# GSM_Voltage_Translator.net
KiCad netlist of a schematic drawn in Altium Designer
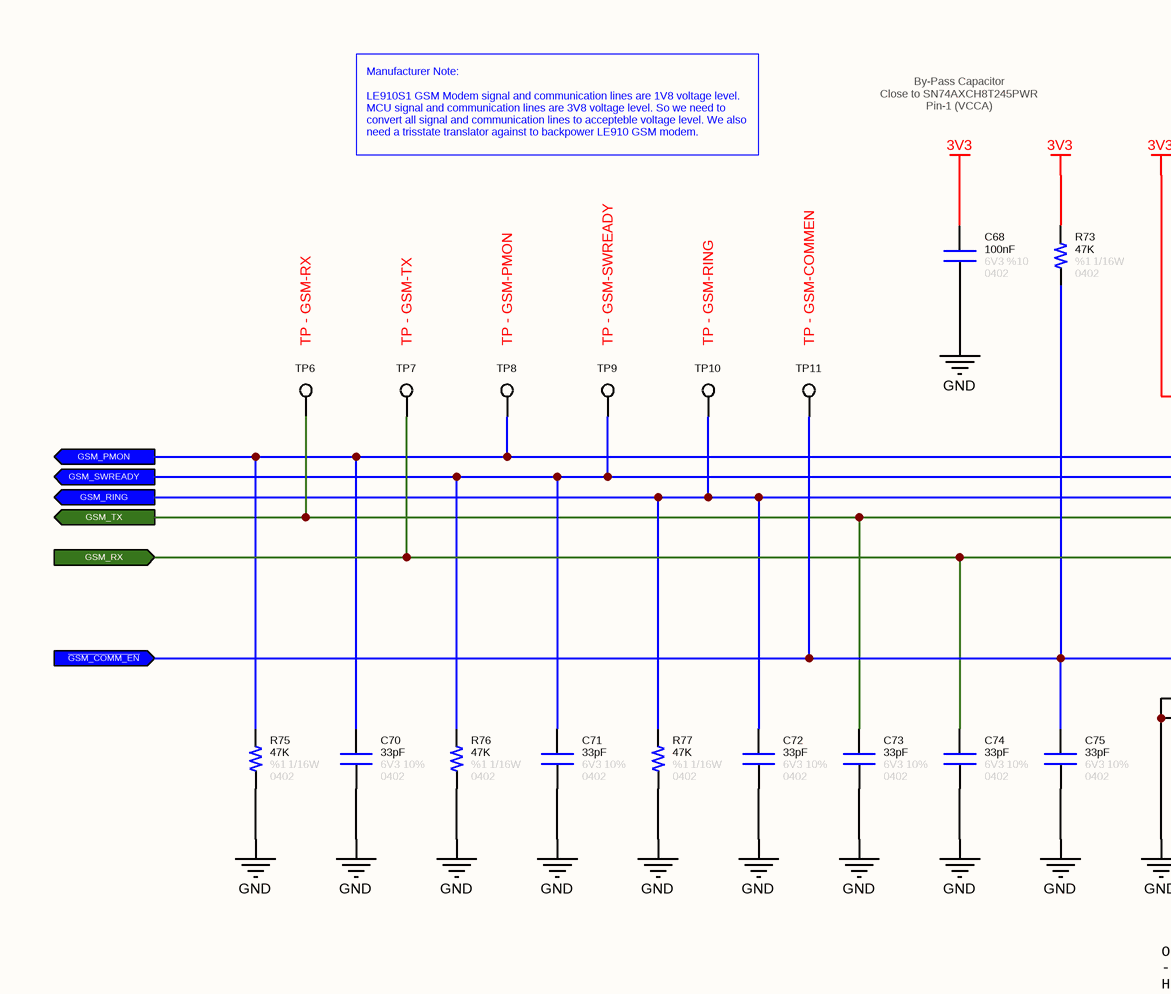
[diagram p0: GSM Voltage Translator.SchDoc, left]
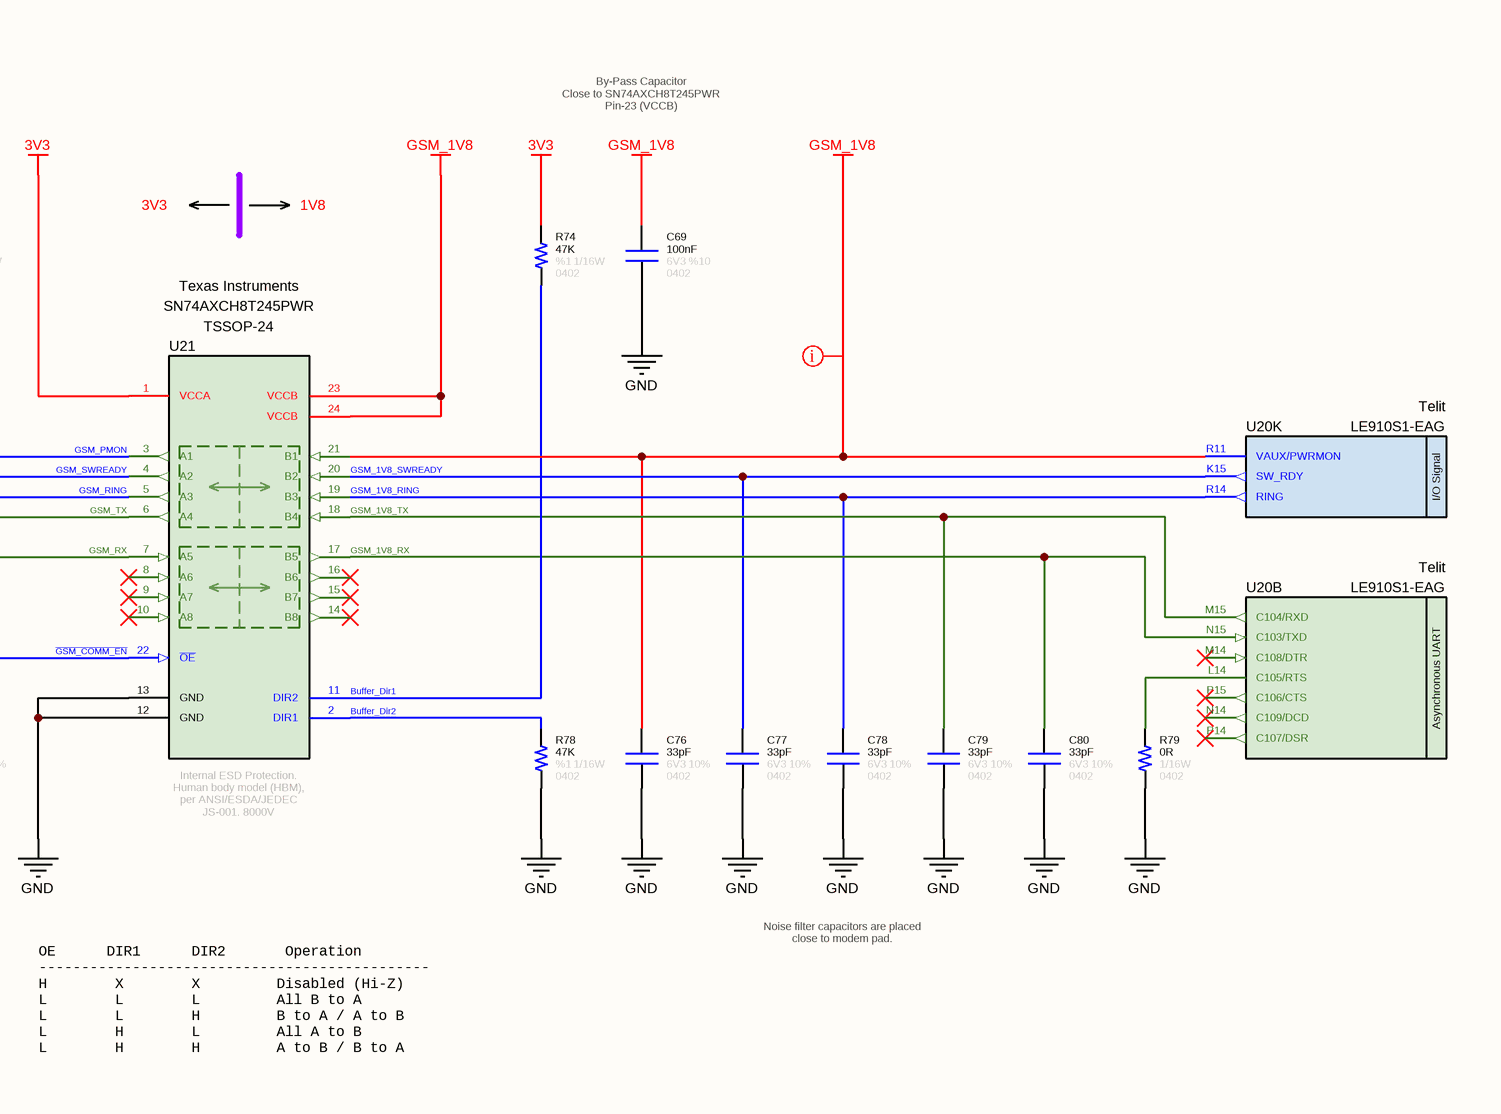
[diagram p1: GSM Voltage Translator.SchDoc, right]

(export (version "E")
  (design (tool "Eeschema 10.0.6"))
  (components
    (comp (ref "C68")
      (value "100nF")
      (footprint "CAPACITOR_0402")
      (description "Capacitor - 100nF [0402-6V3] (Ceramic)")
      (fields
        (field (name "MANUFACTURER PART NUMBER") "04026D104KAT4A")
        (field (name "TOLERANCE") "%10")
        (field (name "VOLTAGE") "6V3")
        (field (name "CASE") "0402")
        (field (name "Comment") "Capacitor - 100nF [0402] (Ceramic)")
      )
      (libsource (lib "Akkoyun") (part "Capacitor - 100nF [0402-6V3]"))
    )
    (comp (ref "C69")
      (value "100nF")
      (footprint "CAPACITOR_0402")
      (description "Capacitor - 100nF [0402-6V3] (Ceramic)")
      (fields
        (field (name "MANUFACTURER PART NUMBER") "04026D104KAT4A")
        (field (name "TOLERANCE") "%10")
        (field (name "VOLTAGE") "6V3")
        (field (name "CASE") "0402")
        (field (name "Comment") "Capacitor - 100nF [0402] (Ceramic)")
      )
      (libsource (lib "Akkoyun") (part "Capacitor - 100nF [0402-6V3]"))
    )
    (comp (ref "C70")
      (value "33pF")
      (footprint "CAPACITOR_0402")
      (description "Capacitor - 33pF [0402] (Ceramic)")
      (fields
        (field (name "MANUFACTURER PART NUMBER") "C0402C330J9RACAUTO")
        (field (name "TOLERANCE") "10%")
        (field (name "CASE") "0402")
        (field (name "VOLTAGE") "6V3")
      )
      (libsource (lib "Akkoyun") (part "Capacitor - 33pF [0402-6V3]"))
    )
    (comp (ref "C71")
      (value "33pF")
      (footprint "CAPACITOR_0402")
      (description "Capacitor - 33pF [0402] (Ceramic)")
      (fields
        (field (name "MANUFACTURER PART NUMBER") "C0402C330J9RACAUTO")
        (field (name "TOLERANCE") "10%")
        (field (name "CASE") "0402")
        (field (name "VOLTAGE") "6V3")
      )
      (libsource (lib "Akkoyun") (part "Capacitor - 33pF [0402-6V3]"))
    )
    (comp (ref "C72")
      (value "33pF")
      (footprint "CAPACITOR_0402")
      (description "Capacitor - 33pF [0402] (Ceramic)")
      (fields
        (field (name "MANUFACTURER PART NUMBER") "C0402C330J9RACAUTO")
        (field (name "TOLERANCE") "10%")
        (field (name "CASE") "0402")
        (field (name "VOLTAGE") "6V3")
      )
      (libsource (lib "Akkoyun") (part "Capacitor - 33pF [0402-6V3]"))
    )
    (comp (ref "C73")
      (value "33pF")
      (footprint "CAPACITOR_0402")
      (description "Capacitor - 33pF [0402] (Ceramic)")
      (fields
        (field (name "MANUFACTURER PART NUMBER") "C0402C330J9RACAUTO")
        (field (name "TOLERANCE") "10%")
        (field (name "CASE") "0402")
        (field (name "VOLTAGE") "6V3")
      )
      (libsource (lib "Akkoyun") (part "Capacitor - 33pF [0402-6V3]"))
    )
    (comp (ref "C74")
      (value "33pF")
      (footprint "CAPACITOR_0402")
      (description "Capacitor - 33pF [0402] (Ceramic)")
      (fields
        (field (name "MANUFACTURER PART NUMBER") "C0402C330J9RACAUTO")
        (field (name "TOLERANCE") "10%")
        (field (name "CASE") "0402")
        (field (name "VOLTAGE") "6V3")
      )
      (libsource (lib "Akkoyun") (part "Capacitor - 33pF [0402-6V3]"))
    )
    (comp (ref "C75")
      (value "33pF")
      (footprint "CAPACITOR_0402")
      (description "Capacitor - 33pF [0402] (Ceramic)")
      (fields
        (field (name "MANUFACTURER PART NUMBER") "C0402C330J9RACAUTO")
        (field (name "TOLERANCE") "10%")
        (field (name "CASE") "0402")
        (field (name "VOLTAGE") "6V3")
      )
      (libsource (lib "Akkoyun") (part "Capacitor - 33pF [0402-6V3]"))
    )
    (comp (ref "C76")
      (value "33pF")
      (footprint "CAPACITOR_0402")
      (description "Capacitor - 33pF [0402] (Ceramic)")
      (fields
        (field (name "MANUFACTURER PART NUMBER") "C0402C330J9RACAUTO")
        (field (name "TOLERANCE") "10%")
        (field (name "CASE") "0402")
        (field (name "VOLTAGE") "6V3")
      )
      (libsource (lib "Akkoyun") (part "Capacitor - 33pF [0402-6V3]"))
    )
    (comp (ref "C77")
      (value "33pF")
      (footprint "CAPACITOR_0402")
      (description "Capacitor - 33pF [0402] (Ceramic)")
      (fields
        (field (name "MANUFACTURER PART NUMBER") "C0402C330J9RACAUTO")
        (field (name "TOLERANCE") "10%")
        (field (name "CASE") "0402")
        (field (name "VOLTAGE") "6V3")
      )
      (libsource (lib "Akkoyun") (part "Capacitor - 33pF [0402-6V3]"))
    )
    (comp (ref "C78")
      (value "33pF")
      (footprint "CAPACITOR_0402")
      (description "Capacitor - 33pF [0402] (Ceramic)")
      (fields
        (field (name "MANUFACTURER PART NUMBER") "C0402C330J9RACAUTO")
        (field (name "TOLERANCE") "10%")
        (field (name "CASE") "0402")
        (field (name "VOLTAGE") "6V3")
      )
      (libsource (lib "Akkoyun") (part "Capacitor - 33pF [0402-6V3]"))
    )
    (comp (ref "C79")
      (value "33pF")
      (footprint "CAPACITOR_0402")
      (description "Capacitor - 33pF [0402] (Ceramic)")
      (fields
        (field (name "MANUFACTURER PART NUMBER") "C0402C330J9RACAUTO")
        (field (name "TOLERANCE") "10%")
        (field (name "CASE") "0402")
        (field (name "VOLTAGE") "6V3")
      )
      (libsource (lib "Akkoyun") (part "Capacitor - 33pF [0402-6V3]"))
    )
    (comp (ref "C80")
      (value "33pF")
      (footprint "CAPACITOR_0402")
      (description "Capacitor - 33pF [0402] (Ceramic)")
      (fields
        (field (name "MANUFACTURER PART NUMBER") "C0402C330J9RACAUTO")
        (field (name "TOLERANCE") "10%")
        (field (name "CASE") "0402")
        (field (name "VOLTAGE") "6V3")
      )
      (libsource (lib "Akkoyun") (part "Capacitor - 33pF [0402-6V3]"))
    )
    (comp (ref "R73")
      (value "47K")
      (footprint "RESISTOR_0402")
      (description "Thick Film Resistors - SMD 1/16 W 47 KOhm 1%")
      (fields
        (field (name "MANUFACTURER PART NUMBER") "CRCW040247K0FKED")
        (field (name "TOLERANCE") "%1")
        (field (name "CASE") "0402")
        (field (name "POWER") "1/16W")
        (field (name "Comment") "47K - 0402 - %1 - 1/16W")
      )
      (libsource (lib "Akkoyun") (part "Resistor - 47K [0402]"))
    )
    (comp (ref "R74")
      (value "47K")
      (footprint "RESISTOR_0402")
      (description "Thick Film Resistors - SMD 1/16 W 47 KOhm 1%")
      (fields
        (field (name "MANUFACTURER PART NUMBER") "CRCW040247K0FKED")
        (field (name "TOLERANCE") "%1")
        (field (name "CASE") "0402")
        (field (name "POWER") "1/16W")
        (field (name "Comment") "47K - 0402 - %1 - 1/16W")
      )
      (libsource (lib "Akkoyun") (part "Resistor - 47K [0402]"))
    )
    (comp (ref "R75")
      (value "47K")
      (footprint "RESISTOR_0402")
      (description "Thick Film Resistors - SMD 1/16 W 47 KOhm 1%")
      (fields
        (field (name "MANUFACTURER PART NUMBER") "CRCW040247K0FKED")
        (field (name "TOLERANCE") "%1")
        (field (name "CASE") "0402")
        (field (name "POWER") "1/16W")
        (field (name "Comment") "47K - 0402 - %1 - 1/16W")
      )
      (libsource (lib "Akkoyun") (part "Resistor - 47K [0402]"))
    )
    (comp (ref "R76")
      (value "47K")
      (footprint "RESISTOR_0402")
      (description "Thick Film Resistors - SMD 1/16 W 47 KOhm 1%")
      (fields
        (field (name "MANUFACTURER PART NUMBER") "CRCW040247K0FKED")
        (field (name "TOLERANCE") "%1")
        (field (name "CASE") "0402")
        (field (name "POWER") "1/16W")
        (field (name "Comment") "47K - 0402 - %1 - 1/16W")
      )
      (libsource (lib "Akkoyun") (part "Resistor - 47K [0402]"))
    )
    (comp (ref "R77")
      (value "47K")
      (footprint "RESISTOR_0402")
      (description "Thick Film Resistors - SMD 1/16 W 47 KOhm 1%")
      (fields
        (field (name "MANUFACTURER PART NUMBER") "CRCW040247K0FKED")
        (field (name "TOLERANCE") "%1")
        (field (name "CASE") "0402")
        (field (name "POWER") "1/16W")
        (field (name "Comment") "47K - 0402 - %1 - 1/16W")
      )
      (libsource (lib "Akkoyun") (part "Resistor - 47K [0402]"))
    )
    (comp (ref "R78")
      (value "47K")
      (footprint "RESISTOR_0402")
      (description "Thick Film Resistors - SMD 1/16 W 47 KOhm 1%")
      (fields
        (field (name "MANUFACTURER PART NUMBER") "CRCW040247K0FKED")
        (field (name "TOLERANCE") "%1")
        (field (name "CASE") "0402")
        (field (name "POWER") "1/16W")
        (field (name "Comment") "47K - 0402 - %1 - 1/16W")
      )
      (libsource (lib "Akkoyun") (part "Resistor - 47K [0402]"))
    )
    (comp (ref "R79")
      (value "0R")
      (footprint "RESISTOR_0402")
      (description "Thick Film Resistors - SMD 1/16 W 0 Ohm")
      (fields
        (field (name "MANUFACTURER PART NUMBER") "CRCW04020000Z0ED")
        (field (name "CASE") "0402")
        (field (name "POWER") "1/16W")
        (field (name "Comment") "0R - 0402 - %1 - 1/16W")
      )
      (libsource (lib "Akkoyun") (part "Resistor - 0R [0402]"))
    )
    (comp (ref "TP6")
      (value "TP - GSM-RX")
      (footprint "TP")
      (description "Test Point")
      (libsource (lib "Akkoyun") (part "PCB - Test Point"))
    )
    (comp (ref "TP7")
      (value "TP - GSM-TX")
      (footprint "TP")
      (description "Test Point")
      (libsource (lib "Akkoyun") (part "PCB - Test Point"))
    )
    (comp (ref "TP8")
      (value "TP - GSM-PMON")
      (footprint "TP")
      (description "Test Point")
      (libsource (lib "Akkoyun") (part "PCB - Test Point"))
    )
    (comp (ref "TP9")
      (value "TP - GSM-SWREADY")
      (footprint "TP")
      (description "Test Point")
      (libsource (lib "Akkoyun") (part "PCB - Test Point"))
    )
    (comp (ref "TP10")
      (value "TP - GSM-RING")
      (footprint "TP")
      (description "Test Point")
      (libsource (lib "Akkoyun") (part "PCB - Test Point"))
    )
    (comp (ref "TP11")
      (value "TP - GSM-COMMEN")
      (footprint "TP")
      (description "Test Point")
      (libsource (lib "Akkoyun") (part "PCB - Test Point"))
    )
    (comp (ref "U20")
      (value "LE910S1-EAG LTE GSM Module")
      (footprint "LE910 GSM Modem")
      (description "Telit LE910S1-EAG GPRS/GNSS Module")
      (fields
        (field (name "MANUFACTURER PART NUMBER") "LE910S1-EAG")
        (field (name "MANUFACTURER NAME") "Telit")
      )
      (libsource (lib "Akkoyun") (part "IC - LE910S1-EAG"))
    )
    (comp (ref "U21")
      (value "SN74AXCH8T245PWR")
      (footprint "TSSOP-24")
      (description "Translation - Voltage Levels 8-Bit Dual-Supply Bus Transceiver 24-TSSOP -40 to 125")
      (fields
        (field (name "MANUFACTURER NAME") "Texas Instruments")
        (field (name "MANUFACTURER PART NUMBER") "SN74AXCH8T245PWR")
        (field (name "CASE") "TSSOP-24")
      )
      (libsource (lib "Akkoyun") (part "IC - SN74AXCH8T245PWR"))
    )
  )
  (nets
    (net (code "1") (name "/Buffer_Dir1") (class "Default")
      (node (ref "R74") (pin "1") (pinfunction "1_1") (pintype "passive"))
      (node (ref "U21") (pin "11") (pinfunction "DIR2_11") (pintype "passive"))
    )
    (net (code "2") (name "/Buffer_Dir2") (class "Default")
      (node (ref "R78") (pin "2") (pinfunction "2_2") (pintype "passive"))
      (node (ref "U21") (pin "2") (pinfunction "DIR1_2") (pintype "passive"))
    )
    (net (code "3") (name "/GSM_1V8_RING") (class "Default")
      (node (ref "C78") (pin "2") (pinfunction "2_2") (pintype "passive"))
      (node (ref "U20") (pin "R14") (pinfunction "RING_R14") (pintype "output"))
      (node (ref "U21") (pin "19") (pinfunction "B3_19") (pintype "input"))
    )
    (net (code "4") (name "/GSM_1V8_RX") (class "Default")
      (node (ref "C80") (pin "2") (pinfunction "2_2") (pintype "passive"))
      (node (ref "U20") (pin "N15") (pinfunction "C103/TXD_N15") (pintype "input"))
      (node (ref "U21") (pin "17") (pinfunction "B5_17") (pintype "output"))
    )
    (net (code "5") (name "/GSM_1V8_SWREADY") (class "Default")
      (node (ref "C77") (pin "2") (pinfunction "2_2") (pintype "passive"))
      (node (ref "U20") (pin "K15") (pinfunction "SW_RDY_K15") (pintype "output"))
      (node (ref "U21") (pin "20") (pinfunction "B2_20") (pintype "input"))
    )
    (net (code "6") (name "/GSM_1V8_TX") (class "Default")
      (node (ref "C79") (pin "2") (pinfunction "2_2") (pintype "passive"))
      (node (ref "U20") (pin "M15") (pinfunction "C104/RXD_M15") (pintype "output"))
      (node (ref "U21") (pin "18") (pinfunction "B4_18") (pintype "input"))
    )
    (net (code "7") (name "/GSM_PMON") (class "Default")
      (node (ref "C70") (pin "2") (pinfunction "2_2") (pintype "passive"))
      (node (ref "R75") (pin "2") (pinfunction "2_2") (pintype "passive"))
      (node (ref "TP8") (pin "1") (pinfunction "1_1") (pintype "passive"))
      (node (ref "U21") (pin "3") (pinfunction "A1_3") (pintype "output"))
    )
    (net (code "8") (name "/GSM_RING") (class "Default")
      (node (ref "C72") (pin "2") (pinfunction "2_2") (pintype "passive"))
      (node (ref "R77") (pin "2") (pinfunction "2_2") (pintype "passive"))
      (node (ref "TP10") (pin "1") (pinfunction "1_1") (pintype "passive"))
      (node (ref "U21") (pin "5") (pinfunction "A3_5") (pintype "output"))
    )
    (net (code "9") (name "/GSM_RX") (class "Default")
      (node (ref "C74") (pin "2") (pinfunction "2_2") (pintype "passive"))
      (node (ref "TP7") (pin "1") (pinfunction "1_1") (pintype "passive"))
      (node (ref "U21") (pin "7") (pinfunction "A5_7") (pintype "input"))
    )
    (net (code "10") (name "/GSM_SWREADY") (class "Default")
      (node (ref "C71") (pin "2") (pinfunction "2_2") (pintype "passive"))
      (node (ref "R76") (pin "2") (pinfunction "2_2") (pintype "passive"))
      (node (ref "TP9") (pin "1") (pinfunction "1_1") (pintype "passive"))
      (node (ref "U21") (pin "4") (pinfunction "A2_4") (pintype "output"))
    )
    (net (code "11") (name "/GSM_TX") (class "Default")
      (node (ref "C73") (pin "2") (pinfunction "2_2") (pintype "passive"))
      (node (ref "TP6") (pin "1") (pinfunction "1_1") (pintype "passive"))
      (node (ref "U21") (pin "6") (pinfunction "A4_6") (pintype "output"))
    )
    (net (code "12") (name "/~{GSM_COMM_EN}") (class "Default")
      (node (ref "C75") (pin "2") (pinfunction "2_2") (pintype "passive"))
      (node (ref "R73") (pin "1") (pinfunction "1_1") (pintype "passive"))
      (node (ref "TP11") (pin "1") (pinfunction "1_1") (pintype "passive"))
      (node (ref "U21") (pin "22") (pinfunction "~{OE}_22") (pintype "input"))
    )
    (net (code "13") (name "3V3") (class "Default")
      (node (ref "C68") (pin "2") (pinfunction "2_2") (pintype "passive"))
      (node (ref "R73") (pin "2") (pinfunction "2_2") (pintype "passive"))
      (node (ref "R74") (pin "2") (pinfunction "2_2") (pintype "passive"))
      (node (ref "U21") (pin "1") (pinfunction "VCCA_1") (pintype "power_in"))
    )
    (net (code "14") (name "GND") (class "Default")
      (node (ref "C68") (pin "1") (pinfunction "1_1") (pintype "passive"))
      (node (ref "C69") (pin "1") (pinfunction "1_1") (pintype "passive"))
      (node (ref "C70") (pin "1") (pinfunction "1_1") (pintype "passive"))
      (node (ref "C71") (pin "1") (pinfunction "1_1") (pintype "passive"))
      (node (ref "C72") (pin "1") (pinfunction "1_1") (pintype "passive"))
      (node (ref "C73") (pin "1") (pinfunction "1_1") (pintype "passive"))
      (node (ref "C74") (pin "1") (pinfunction "1_1") (pintype "passive"))
      (node (ref "C75") (pin "1") (pinfunction "1_1") (pintype "passive"))
      (node (ref "C76") (pin "1") (pinfunction "1_1") (pintype "passive"))
      (node (ref "C77") (pin "1") (pinfunction "1_1") (pintype "passive"))
      (node (ref "C78") (pin "1") (pinfunction "1_1") (pintype "passive"))
      (node (ref "C79") (pin "1") (pinfunction "1_1") (pintype "passive"))
      (node (ref "C80") (pin "1") (pinfunction "1_1") (pintype "passive"))
      (node (ref "R75") (pin "1") (pinfunction "1_1") (pintype "passive"))
      (node (ref "R76") (pin "1") (pinfunction "1_1") (pintype "passive"))
      (node (ref "R77") (pin "1") (pinfunction "1_1") (pintype "passive"))
      (node (ref "R78") (pin "1") (pinfunction "1_1") (pintype "passive"))
      (node (ref "R79") (pin "1") (pinfunction "1_1") (pintype "passive"))
      (node (ref "U21") (pin "12") (pinfunction "GND_12") (pintype "power_in"))
      (node (ref "U21") (pin "13") (pinfunction "GND_13") (pintype "power_in"))
    )
    (net (code "15") (name "GSM_1V8") (class "Default")
      (node (ref "C69") (pin "2") (pinfunction "2_2") (pintype "passive"))
      (node (ref "C76") (pin "2") (pinfunction "2_2") (pintype "passive"))
      (node (ref "U20") (pin "R11") (pinfunction "VAUX/PWRMON_R11") (pintype "power_in"))
      (node (ref "U21") (pin "21") (pinfunction "B1_21") (pintype "input"))
      (node (ref "U21") (pin "23") (pinfunction "VCCB_23") (pintype "power_in"))
      (node (ref "U21") (pin "24") (pinfunction "VCCB_24") (pintype "power_in"))
    )
    (net (code "16") (name "Net-(U20B-C105{slash}RTS)") (class "Default")
      (node (ref "R79") (pin "2") (pinfunction "2_2") (pintype "passive"))
      (node (ref "U20") (pin "L14") (pinfunction "C105/RTS_L14") (pintype "open_collector"))
    )
    (net (code "17") (name "unconnected-(U20B-C106{slash}CTS-PadP15)") (class "Default")
      (node (ref "U20") (pin "P15") (pinfunction "C106/CTS_P15") (pintype "output+no_connect"))
    )
    (net (code "18") (name "unconnected-(U20B-C107{slash}DSR-PadP14)") (class "Default")
      (node (ref "U20") (pin "P14") (pinfunction "C107/DSR_P14") (pintype "output+no_connect"))
    )
    (net (code "19") (name "unconnected-(U20B-C108{slash}DTR-PadM14)") (class "Default")
      (node (ref "U20") (pin "M14") (pinfunction "C108/DTR_M14") (pintype "input+no_connect"))
    )
    (net (code "20") (name "unconnected-(U20B-C109{slash}DCD-PadN14)") (class "Default")
      (node (ref "U20") (pin "N14") (pinfunction "C109/DCD_N14") (pintype "output+no_connect"))
    )
    (net (code "21") (name "unconnected-(U21-A6-Pad8)") (class "Default")
      (node (ref "U21") (pin "8") (pinfunction "A6_8") (pintype "input+no_connect"))
    )
    (net (code "22") (name "unconnected-(U21-A7-Pad9)") (class "Default")
      (node (ref "U21") (pin "9") (pinfunction "A7_9") (pintype "input+no_connect"))
    )
    (net (code "23") (name "unconnected-(U21-A8-Pad10)") (class "Default")
      (node (ref "U21") (pin "10") (pinfunction "A8_10") (pintype "input+no_connect"))
    )
    (net (code "24") (name "unconnected-(U21-B6-Pad16)") (class "Default")
      (node (ref "U21") (pin "16") (pinfunction "B6_16") (pintype "output+no_connect"))
    )
    (net (code "25") (name "unconnected-(U21-B7-Pad15)") (class "Default")
      (node (ref "U21") (pin "15") (pinfunction "B7_15") (pintype "output+no_connect"))
    )
    (net (code "26") (name "unconnected-(U21-B8-Pad14)") (class "Default")
      (node (ref "U21") (pin "14") (pinfunction "B8_14") (pintype "output+no_connect"))
    )
  )
)
